# bandpass-triple.net
KiCad netlist of a schematic drawn in EAGLE
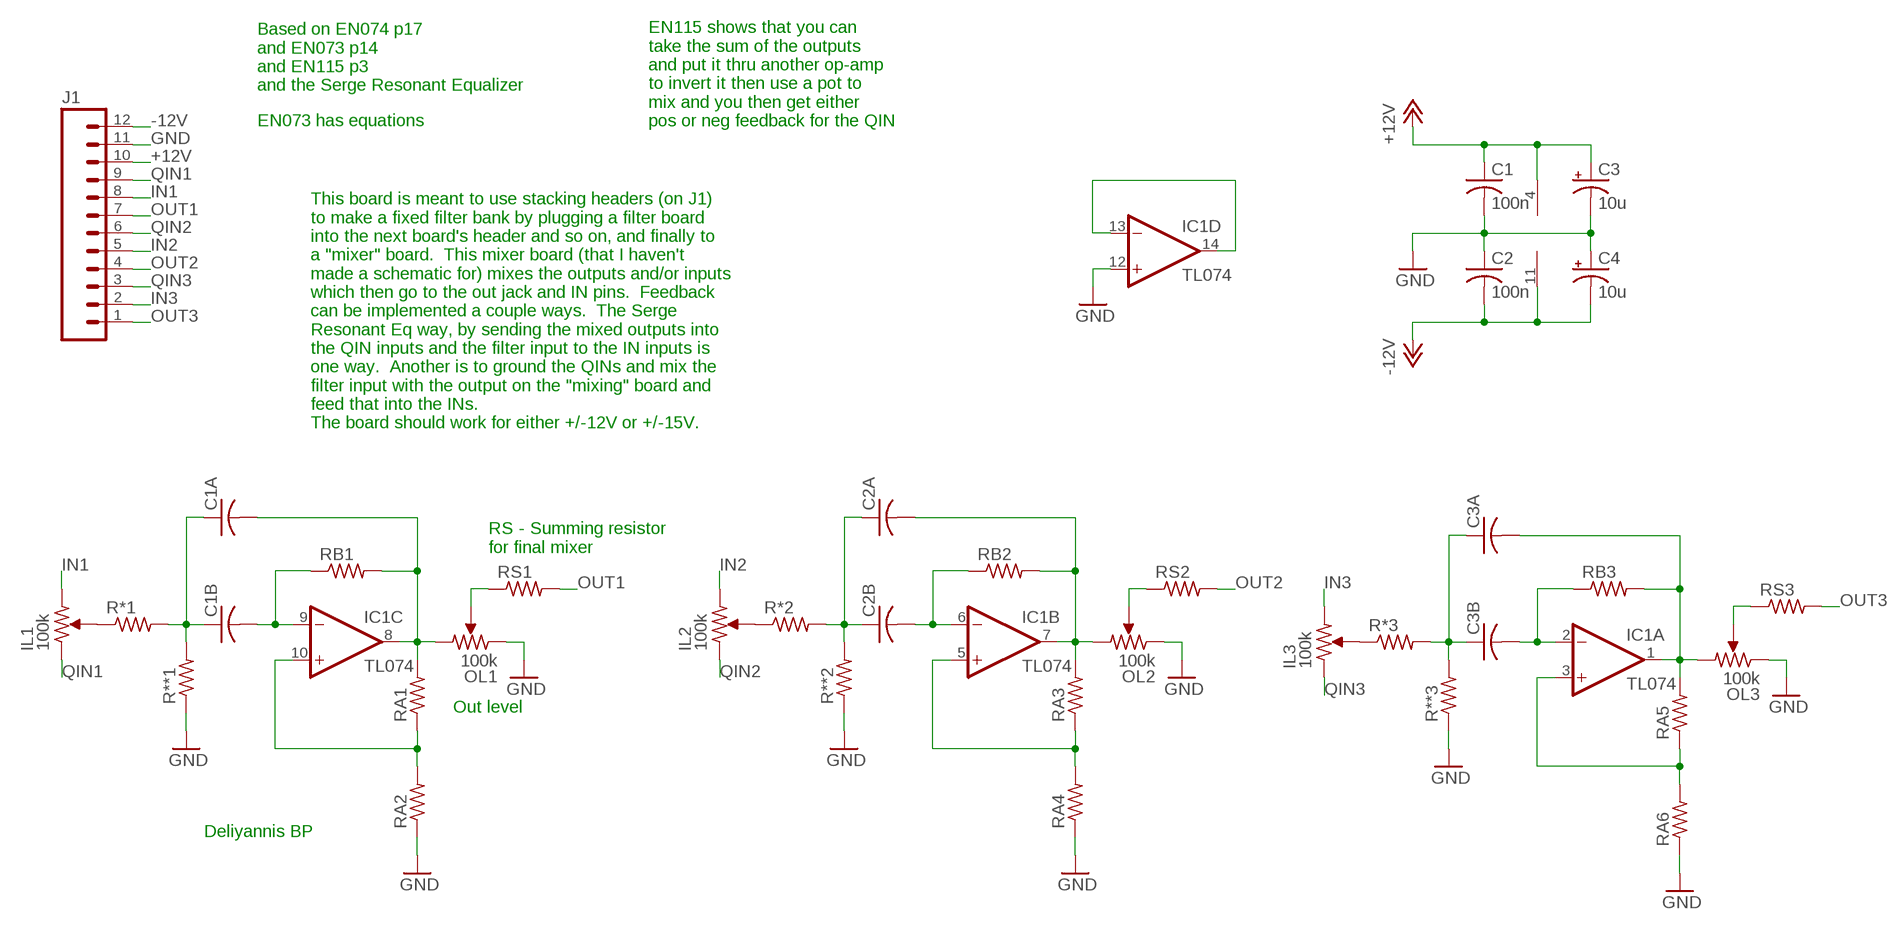
[diagram p0: schematic, sheet 1]

(export (version "E")
  (design (tool "Eeschema 10.0.6"))
  (components
    (comp (ref "C1")
      (value "100n")
      (footprint "eagle-import:C050-025X075")
      (libsource (lib "eagle-import") (part "C-US050-025X075"))
    )
    (comp (ref "C1A")
      (value "C-US050-025X075")
      (footprint "eagle-import:C050-025X075")
      (libsource (lib "eagle-import") (part "C-US050-025X075"))
    )
    (comp (ref "C1B")
      (value "C-US050-025X075")
      (footprint "eagle-import:C050-025X075")
      (libsource (lib "eagle-import") (part "C-US050-025X075"))
    )
    (comp (ref "C2")
      (value "100n")
      (footprint "eagle-import:C050-025X075")
      (libsource (lib "eagle-import") (part "C-US050-025X075"))
    )
    (comp (ref "C2A")
      (value "C-US050-025X075")
      (footprint "eagle-import:C050-025X075")
      (libsource (lib "eagle-import") (part "C-US050-025X075"))
    )
    (comp (ref "C2B")
      (value "C-US050-025X075")
      (footprint "eagle-import:C050-025X075")
      (libsource (lib "eagle-import") (part "C-US050-025X075"))
    )
    (comp (ref "C3")
      (value "10u")
      (footprint "eagle-import:E2,5-5")
      (libsource (lib "eagle-import") (part "CPOL-USE2.5-5"))
    )
    (comp (ref "C3A")
      (value "C-US050-025X075")
      (footprint "eagle-import:C050-025X075")
      (libsource (lib "eagle-import") (part "C-US050-025X075"))
    )
    (comp (ref "C3B")
      (value "C-US050-025X075")
      (footprint "eagle-import:C050-025X075")
      (libsource (lib "eagle-import") (part "C-US050-025X075"))
    )
    (comp (ref "C4")
      (value "10u")
      (footprint "eagle-import:E2,5-5")
      (libsource (lib "eagle-import") (part "CPOL-USE2.5-5"))
    )
    (comp (ref "IC1")
      (value "TL074")
      (footprint "eagle-import:DIL14")
      (libsource (lib "eagle-import") (part "TL074-TOPP"))
    )
    (comp (ref "IL1")
      (value "100k")
      (footprint "eagle-import:POT-BOURNS-PTD901-2015K")
      (libsource (lib "eagle-import") (part "POT-BOURNS-PTD901-2015K"))
    )
    (comp (ref "IL2")
      (value "100k")
      (footprint "eagle-import:POT-BOURNS-PTD901-2015K")
      (libsource (lib "eagle-import") (part "POT-BOURNS-PTD901-2015K"))
    )
    (comp (ref "IL3")
      (value "100k")
      (footprint "eagle-import:POT-BOURNS-PTD901-2015K")
      (libsource (lib "eagle-import") (part "POT-BOURNS-PTD901-2015K"))
    )
    (comp (ref "J1")
      (value "M12LONGPADS")
      (footprint "eagle-import:1X12_LONGPADS")
      (libsource (lib "eagle-import") (part "M12LONGPADS"))
    )
    (comp (ref "OL1")
      (value "100k")
      (footprint "eagle-import:POT-BOURNS-PTD901-2015K")
      (libsource (lib "eagle-import") (part "POT-BOURNS-PTD901-2015K"))
    )
    (comp (ref "OL2")
      (value "100k")
      (footprint "eagle-import:POT-BOURNS-PTD901-2015K")
      (libsource (lib "eagle-import") (part "POT-BOURNS-PTD901-2015K"))
    )
    (comp (ref "OL3")
      (value "100k")
      (footprint "eagle-import:POT-BOURNS-PTD901-2015K")
      (libsource (lib "eagle-import") (part "POT-BOURNS-PTD901-2015K"))
    )
    (comp (ref "R**1")
      (value "R-US_0207/10")
      (footprint "eagle-import:0207_10")
      (libsource (lib "eagle-import") (part "R-US_0207/10"))
    )
    (comp (ref "R**2")
      (value "R-US_0207/10")
      (footprint "eagle-import:0207_10")
      (libsource (lib "eagle-import") (part "R-US_0207/10"))
    )
    (comp (ref "R**3")
      (value "R-US_0207/10")
      (footprint "eagle-import:0207_10")
      (libsource (lib "eagle-import") (part "R-US_0207/10"))
    )
    (comp (ref "R*1")
      (value "R-US_0207/10")
      (footprint "eagle-import:0207_10")
      (libsource (lib "eagle-import") (part "R-US_0207/10"))
    )
    (comp (ref "R*2")
      (value "R-US_0207/10")
      (footprint "eagle-import:0207_10")
      (libsource (lib "eagle-import") (part "R-US_0207/10"))
    )
    (comp (ref "R*3")
      (value "R-US_0207/10")
      (footprint "eagle-import:0207_10")
      (libsource (lib "eagle-import") (part "R-US_0207/10"))
    )
    (comp (ref "RA1")
      (value "R-US_0207/10")
      (footprint "eagle-import:0207_10")
      (libsource (lib "eagle-import") (part "R-US_0207/10"))
    )
    (comp (ref "RA2")
      (value "R-US_0207/10")
      (footprint "eagle-import:0207_10")
      (libsource (lib "eagle-import") (part "R-US_0207/10"))
    )
    (comp (ref "RA3")
      (value "R-US_0207/10")
      (footprint "eagle-import:0207_10")
      (libsource (lib "eagle-import") (part "R-US_0207/10"))
    )
    (comp (ref "RA4")
      (value "R-US_0207/10")
      (footprint "eagle-import:0207_10")
      (libsource (lib "eagle-import") (part "R-US_0207/10"))
    )
    (comp (ref "RA5")
      (value "R-US_0207/10")
      (footprint "eagle-import:0207_10")
      (libsource (lib "eagle-import") (part "R-US_0207/10"))
    )
    (comp (ref "RA6")
      (value "R-US_0207/10")
      (footprint "eagle-import:0207_10")
      (libsource (lib "eagle-import") (part "R-US_0207/10"))
    )
    (comp (ref "RB1")
      (value "R-US_0207/2V")
      (footprint "eagle-import:0207_2V")
      (libsource (lib "eagle-import") (part "R-US_0207/2V"))
    )
    (comp (ref "RB2")
      (value "R-US_0207/2V")
      (footprint "eagle-import:0207_2V")
      (libsource (lib "eagle-import") (part "R-US_0207/2V"))
    )
    (comp (ref "RB3")
      (value "R-US_0207/2V")
      (footprint "eagle-import:0207_2V")
      (libsource (lib "eagle-import") (part "R-US_0207/2V"))
    )
    (comp (ref "RS1")
      (value "R-US_0207/10")
      (footprint "eagle-import:0207_10")
      (libsource (lib "eagle-import") (part "R-US_0207/10"))
    )
    (comp (ref "RS2")
      (value "R-US_0207/10")
      (footprint "eagle-import:0207_10")
      (libsource (lib "eagle-import") (part "R-US_0207/10"))
    )
    (comp (ref "RS3")
      (value "R-US_0207/10")
      (footprint "eagle-import:0207_10")
      (libsource (lib "eagle-import") (part "R-US_0207/10"))
    )
  )
  (nets
    (net (code "1") (name "+12V") (class "Default")
      (node (ref "C1") (pin "1") (pinfunction "1_1") (pintype "passive"))
      (node (ref "C3") (pin "+") (pinfunction "+_+") (pintype "passive"))
      (node (ref "IC1") (pin "4") (pinfunction "V+_4") (pintype "power_in"))
      (node (ref "J1") (pin "10") (pinfunction "10_10") (pintype "passive"))
    )
    (net (code "2") (name "-12V") (class "Default")
      (node (ref "C2") (pin "2") (pinfunction "2_2") (pintype "passive"))
      (node (ref "C4") (pin "-") (pinfunction "-_-") (pintype "passive"))
      (node (ref "IC1") (pin "11") (pinfunction "V-_11") (pintype "power_in"))
      (node (ref "J1") (pin "12") (pinfunction "12_12") (pintype "passive"))
    )
    (net (code "3") (name "/IN1") (class "Default")
      (node (ref "IL1") (pin "1") (pinfunction "1_1") (pintype "passive"))
      (node (ref "J1") (pin "8") (pinfunction "8_8") (pintype "passive"))
    )
    (net (code "4") (name "/IN2") (class "Default")
      (node (ref "IL2") (pin "1") (pinfunction "1_1") (pintype "passive"))
      (node (ref "J1") (pin "5") (pinfunction "5_5") (pintype "passive"))
    )
    (net (code "5") (name "/IN3") (class "Default")
      (node (ref "IL3") (pin "1") (pinfunction "1_1") (pintype "passive"))
      (node (ref "J1") (pin "2") (pinfunction "2_2") (pintype "passive"))
    )
    (net (code "6") (name "/OUT1") (class "Default")
      (node (ref "J1") (pin "7") (pinfunction "7_7") (pintype "passive"))
      (node (ref "RS1") (pin "2") (pinfunction "2_2") (pintype "passive"))
    )
    (net (code "7") (name "/OUT2") (class "Default")
      (node (ref "J1") (pin "4") (pinfunction "4_4") (pintype "passive"))
      (node (ref "RS2") (pin "2") (pinfunction "2_2") (pintype "passive"))
    )
    (net (code "8") (name "/OUT3") (class "Default")
      (node (ref "J1") (pin "1") (pinfunction "1_1") (pintype "passive"))
      (node (ref "RS3") (pin "2") (pinfunction "2_2") (pintype "passive"))
    )
    (net (code "9") (name "/QIN1") (class "Default")
      (node (ref "IL1") (pin "3") (pinfunction "3_3") (pintype "passive"))
      (node (ref "J1") (pin "9") (pinfunction "9_9") (pintype "passive"))
    )
    (net (code "10") (name "/QIN2") (class "Default")
      (node (ref "IL2") (pin "3") (pinfunction "3_3") (pintype "passive"))
      (node (ref "J1") (pin "6") (pinfunction "6_6") (pintype "passive"))
    )
    (net (code "11") (name "/QIN3") (class "Default")
      (node (ref "IL3") (pin "3") (pinfunction "3_3") (pintype "passive"))
      (node (ref "J1") (pin "3") (pinfunction "3_3") (pintype "passive"))
    )
    (net (code "12") (name "GND") (class "Default")
      (node (ref "C1") (pin "2") (pinfunction "2_2") (pintype "passive"))
      (node (ref "C2") (pin "1") (pinfunction "1_1") (pintype "passive"))
      (node (ref "C3") (pin "-") (pinfunction "-_-") (pintype "passive"))
      (node (ref "C4") (pin "+") (pinfunction "+_+") (pintype "passive"))
      (node (ref "IC1") (pin "12") (pinfunction "+IN_12") (pintype "input"))
      (node (ref "J1") (pin "11") (pinfunction "11_11") (pintype "passive"))
      (node (ref "OL1") (pin "3") (pinfunction "3_3") (pintype "passive"))
      (node (ref "OL2") (pin "3") (pinfunction "3_3") (pintype "passive"))
      (node (ref "OL3") (pin "3") (pinfunction "3_3") (pintype "passive"))
      (node (ref "R**1") (pin "1") (pinfunction "1_1") (pintype "passive"))
      (node (ref "R**2") (pin "1") (pinfunction "1_1") (pintype "passive"))
      (node (ref "R**3") (pin "1") (pinfunction "1_1") (pintype "passive"))
      (node (ref "RA2") (pin "1") (pinfunction "1_1") (pintype "passive"))
      (node (ref "RA4") (pin "1") (pinfunction "1_1") (pintype "passive"))
      (node (ref "RA6") (pin "1") (pinfunction "1_1") (pintype "passive"))
    )
    (net (code "13") (name "Net-(C1A-Pad1)") (class "Default")
      (node (ref "C1A") (pin "1") (pinfunction "1_1") (pintype "passive"))
      (node (ref "C1B") (pin "1") (pinfunction "1_1") (pintype "passive"))
      (node (ref "R**1") (pin "2") (pinfunction "2_2") (pintype "passive"))
      (node (ref "R*1") (pin "2") (pinfunction "2_2") (pintype "passive"))
    )
    (net (code "14") (name "Net-(C2A-Pad1)") (class "Default")
      (node (ref "C2A") (pin "1") (pinfunction "1_1") (pintype "passive"))
      (node (ref "C2B") (pin "1") (pinfunction "1_1") (pintype "passive"))
      (node (ref "R**2") (pin "2") (pinfunction "2_2") (pintype "passive"))
      (node (ref "R*2") (pin "2") (pinfunction "2_2") (pintype "passive"))
    )
    (net (code "15") (name "Net-(C3A-Pad1)") (class "Default")
      (node (ref "C3A") (pin "1") (pinfunction "1_1") (pintype "passive"))
      (node (ref "C3B") (pin "1") (pinfunction "1_1") (pintype "passive"))
      (node (ref "R**3") (pin "2") (pinfunction "2_2") (pintype "passive"))
      (node (ref "R*3") (pin "2") (pinfunction "2_2") (pintype "passive"))
    )
    (net (code "16") (name "Net-(IC1A-+IN)") (class "Default")
      (node (ref "IC1") (pin "3") (pinfunction "+IN_3") (pintype "input"))
      (node (ref "RA5") (pin "1") (pinfunction "1_1") (pintype "passive"))
      (node (ref "RA6") (pin "2") (pinfunction "2_2") (pintype "passive"))
    )
    (net (code "17") (name "Net-(IC1A--IN)") (class "Default")
      (node (ref "C3B") (pin "2") (pinfunction "2_2") (pintype "passive"))
      (node (ref "IC1") (pin "2") (pinfunction "-IN_2") (pintype "input"))
      (node (ref "RB3") (pin "1") (pinfunction "1_1") (pintype "passive"))
    )
    (net (code "18") (name "Net-(IC1A-OUT)") (class "Default")
      (node (ref "C3A") (pin "2") (pinfunction "2_2") (pintype "passive"))
      (node (ref "IC1") (pin "1") (pinfunction "OUT_1") (pintype "output"))
      (node (ref "OL3") (pin "1") (pinfunction "1_1") (pintype "passive"))
      (node (ref "RA5") (pin "2") (pinfunction "2_2") (pintype "passive"))
      (node (ref "RB3") (pin "2") (pinfunction "2_2") (pintype "passive"))
    )
    (net (code "19") (name "Net-(IC1B-+IN)") (class "Default")
      (node (ref "IC1") (pin "5") (pinfunction "+IN_5") (pintype "input"))
      (node (ref "RA3") (pin "1") (pinfunction "1_1") (pintype "passive"))
      (node (ref "RA4") (pin "2") (pinfunction "2_2") (pintype "passive"))
    )
    (net (code "20") (name "Net-(IC1B--IN)") (class "Default")
      (node (ref "C2B") (pin "2") (pinfunction "2_2") (pintype "passive"))
      (node (ref "IC1") (pin "6") (pinfunction "-IN_6") (pintype "input"))
      (node (ref "RB2") (pin "1") (pinfunction "1_1") (pintype "passive"))
    )
    (net (code "21") (name "Net-(IC1B-OUT)") (class "Default")
      (node (ref "C2A") (pin "2") (pinfunction "2_2") (pintype "passive"))
      (node (ref "IC1") (pin "7") (pinfunction "OUT_7") (pintype "output"))
      (node (ref "OL2") (pin "1") (pinfunction "1_1") (pintype "passive"))
      (node (ref "RA3") (pin "2") (pinfunction "2_2") (pintype "passive"))
      (node (ref "RB2") (pin "2") (pinfunction "2_2") (pintype "passive"))
    )
    (net (code "22") (name "Net-(IC1C-+IN)") (class "Default")
      (node (ref "IC1") (pin "10") (pinfunction "+IN_10") (pintype "input"))
      (node (ref "RA1") (pin "1") (pinfunction "1_1") (pintype "passive"))
      (node (ref "RA2") (pin "2") (pinfunction "2_2") (pintype "passive"))
    )
    (net (code "23") (name "Net-(IC1C--IN)") (class "Default")
      (node (ref "C1B") (pin "2") (pinfunction "2_2") (pintype "passive"))
      (node (ref "IC1") (pin "9") (pinfunction "-IN_9") (pintype "input"))
      (node (ref "RB1") (pin "1") (pinfunction "1_1") (pintype "passive"))
    )
    (net (code "24") (name "Net-(IC1C-OUT)") (class "Default")
      (node (ref "C1A") (pin "2") (pinfunction "2_2") (pintype "passive"))
      (node (ref "IC1") (pin "8") (pinfunction "OUT_8") (pintype "output"))
      (node (ref "OL1") (pin "1") (pinfunction "1_1") (pintype "passive"))
      (node (ref "RA1") (pin "2") (pinfunction "2_2") (pintype "passive"))
      (node (ref "RB1") (pin "2") (pinfunction "2_2") (pintype "passive"))
    )
    (net (code "25") (name "Net-(IC1D--IN)") (class "Default")
      (node (ref "IC1") (pin "13") (pinfunction "-IN_13") (pintype "input"))
      (node (ref "IC1") (pin "14") (pinfunction "OUT_14") (pintype "output"))
    )
    (net (code "26") (name "Net-(IL1-Pad2)") (class "Default")
      (node (ref "IL1") (pin "2") (pinfunction "2_2") (pintype "passive"))
      (node (ref "R*1") (pin "1") (pinfunction "1_1") (pintype "passive"))
    )
    (net (code "27") (name "Net-(IL2-Pad2)") (class "Default")
      (node (ref "IL2") (pin "2") (pinfunction "2_2") (pintype "passive"))
      (node (ref "R*2") (pin "1") (pinfunction "1_1") (pintype "passive"))
    )
    (net (code "28") (name "Net-(IL3-Pad2)") (class "Default")
      (node (ref "IL3") (pin "2") (pinfunction "2_2") (pintype "passive"))
      (node (ref "R*3") (pin "1") (pinfunction "1_1") (pintype "passive"))
    )
    (net (code "29") (name "Net-(OL1-Pad2)") (class "Default")
      (node (ref "OL1") (pin "2") (pinfunction "2_2") (pintype "passive"))
      (node (ref "RS1") (pin "1") (pinfunction "1_1") (pintype "passive"))
    )
    (net (code "30") (name "Net-(OL2-Pad2)") (class "Default")
      (node (ref "OL2") (pin "2") (pinfunction "2_2") (pintype "passive"))
      (node (ref "RS2") (pin "1") (pinfunction "1_1") (pintype "passive"))
    )
    (net (code "31") (name "Net-(OL3-Pad2)") (class "Default")
      (node (ref "OL3") (pin "2") (pinfunction "2_2") (pintype "passive"))
      (node (ref "RS3") (pin "1") (pinfunction "1_1") (pintype "passive"))
    )
  )
)
